# Devre_2_Proje.net
KiCad netlist of a schematic drawn in Altium Designer
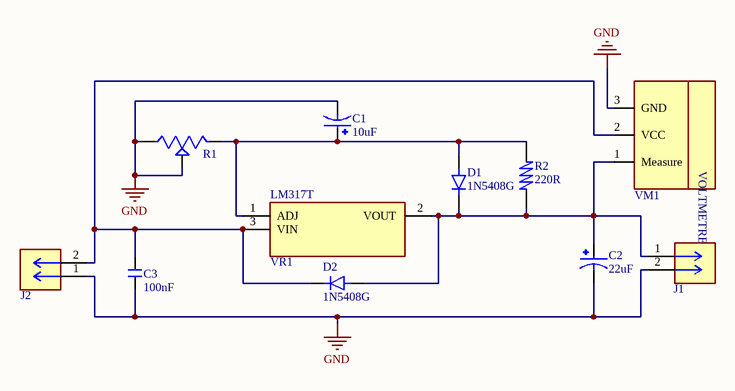
[diagram p0: Devre_2_Proje.SchDoc]

(export (version "E")
  (design (tool "Eeschema 10.0.6"))
  (components
    (comp (ref "C1")
      (value "10uF")
      (footprint "CAP-ELEC")
      (description "CAP-ELEC 10 uF")
      (libsource (lib "Devre_2_Proje") (part "CAP ELEC 10uF"))
    )
    (comp (ref "C2")
      (value "22uF")
      (footprint "CAP-ELEC")
      (description "CAP-ELEC 22 uF")
      (libsource (lib "Devre_2_Proje") (part "CAP ELEC 22uF"))
    )
    (comp (ref "C3")
      (value "100nF")
      (footprint "CAP-CER-100nF")
      (description "0.1uF (100nF)")
      (libsource (lib "Devre_2_Proje") (part "CAP CER"))
    )
    (comp (ref "D1")
      (value "1N5408G")
      (footprint "DIODE_1N5408")
      (description "3A, 1000V, Standard Rectifier")
      (fields (field (name "MF") "Taiwan Semiconductor"))
      (libsource (lib "Devre_2_Proje") (part "1N5408G"))
    )
    (comp (ref "D2")
      (value "1N5408G")
      (footprint "DIODE_1N5408")
      (description "3A, 1000V, Standard Rectifier")
      (fields (field (name "MF") "Taiwan Semiconductor"))
      (libsource (lib "Devre_2_Proje") (part "1N5408G"))
    )
    (comp (ref "J1")
      (value "TERM BLK 1x2P 5.08mm")
      (footprint "Term_Block_5.08mm-1x2P")
      (fields (field (name "MF") "Phoenix Contact") (field (name "MP") "MKDS 1,5/ 2-5,08"))
      (libsource (lib "") (part "TERM BLK 1x2P 5.08mm_1"))
    )
    (comp (ref "J2")
      (value "TERM BLK 1x2P 5.08mm")
      (footprint "Term_Block_5.08mm-1x2P")
      (fields (field (name "MF") "Phoenix Contact") (field (name "MP") "MKDS 1,5/ 2-5,08"))
      (libsource (lib "Devre_2_Proje") (part "TERM BLK 1x2P 5.08mm"))
    )
    (comp (ref "R1")
      (value "POT")
      (footprint "POT")
      (description "16mm Rotary Potentiometers")
      (fields (field (name "MF") "Kls electronics") (field (name "MP") "WH148-1A-2-18T-L20"))
      (libsource (lib "Devre_2_Proje") (part "POT"))
    )
    (comp (ref "R2")
      (value "220R")
      (footprint "RES-AXIAL-0.7")
      (description "RES 220R 2W\r\nAXIAL-0.7")
      (libsource (lib "Devre_2_Proje") (part "RES 220R"))
    )
    (comp (ref "VM1")
      (value "Voltmetre")
      (footprint "Voltmetre")
      (description "Voltmetre 3 kablolu 0-100V")
      (libsource (lib "Devre_2_Proje") (part "Voltmetre"))
    )
    (comp (ref "VR1")
      (value "LM317T")
      (footprint "LM317T")
      (description "Linear Voltage Regulator IC Positive Adjustable 1 Output 1.5A TO-220AB")
      (fields (field (name "MF") "onsemi"))
      (libsource (lib "Devre_2_Proje") (part "LM317T"))
    )
  )
  (nets
    (net (code "1") (name "GND") (class "Default")
      (node (ref "C1") (pin "2") (pinfunction "2_2") (pintype "passive"))
      (node (ref "C2") (pin "2") (pinfunction "2_2") (pintype "passive"))
      (node (ref "C3") (pin "1") (pinfunction "1_1") (pintype "passive"))
      (node (ref "J1") (pin "2") (pinfunction "2_2") (pintype "passive"))
      (node (ref "J2") (pin "1") (pinfunction "1_1") (pintype "passive"))
      (node (ref "R1") (pin "1") (pinfunction "1_1") (pintype "passive"))
      (node (ref "R1") (pin "2") (pinfunction "2_2") (pintype "passive"))
      (node (ref "VM1") (pin "3") (pinfunction "GND_3") (pintype "passive"))
    )
    (net (code "2") (name "Net-(D1-K)") (class "Default")
      (node (ref "C2") (pin "1") (pinfunction "1_1") (pintype "passive"))
      (node (ref "D1") (pin "C") (pinfunction "K_C") (pintype "passive"))
      (node (ref "D2") (pin "A") (pinfunction "A_A") (pintype "passive"))
      (node (ref "J1") (pin "1") (pinfunction "1_1") (pintype "passive"))
      (node (ref "R2") (pin "1") (pinfunction "1_1") (pintype "passive"))
      (node (ref "VM1") (pin "1") (pinfunction "Measure_1") (pintype "passive"))
      (node (ref "VR1") (pin "2") (pinfunction "VOUT_2") (pintype "passive"))
    )
    (net (code "3") (name "Net-(D2-K)") (class "Default")
      (node (ref "C3") (pin "2") (pinfunction "2_2") (pintype "passive"))
      (node (ref "D2") (pin "C") (pinfunction "K_C") (pintype "passive"))
      (node (ref "J2") (pin "2") (pinfunction "2_2") (pintype "passive"))
      (node (ref "VM1") (pin "2") (pinfunction "VCC_2") (pintype "passive"))
      (node (ref "VR1") (pin "3") (pinfunction "VIN_3") (pintype "passive"))
    )
    (net (code "4") (name "Net-(VR1-ADJ)") (class "Default")
      (node (ref "C1") (pin "1") (pinfunction "1_1") (pintype "passive"))
      (node (ref "D1") (pin "A") (pinfunction "A_A") (pintype "passive"))
      (node (ref "R1") (pin "3") (pinfunction "3_3") (pintype "passive"))
      (node (ref "R2") (pin "2") (pinfunction "2_2") (pintype "passive"))
      (node (ref "VR1") (pin "1") (pinfunction "ADJ_1") (pintype "passive"))
    )
  )
)
